# ES1050.net
KiCad netlist of a schematic drawn in Altium Designer
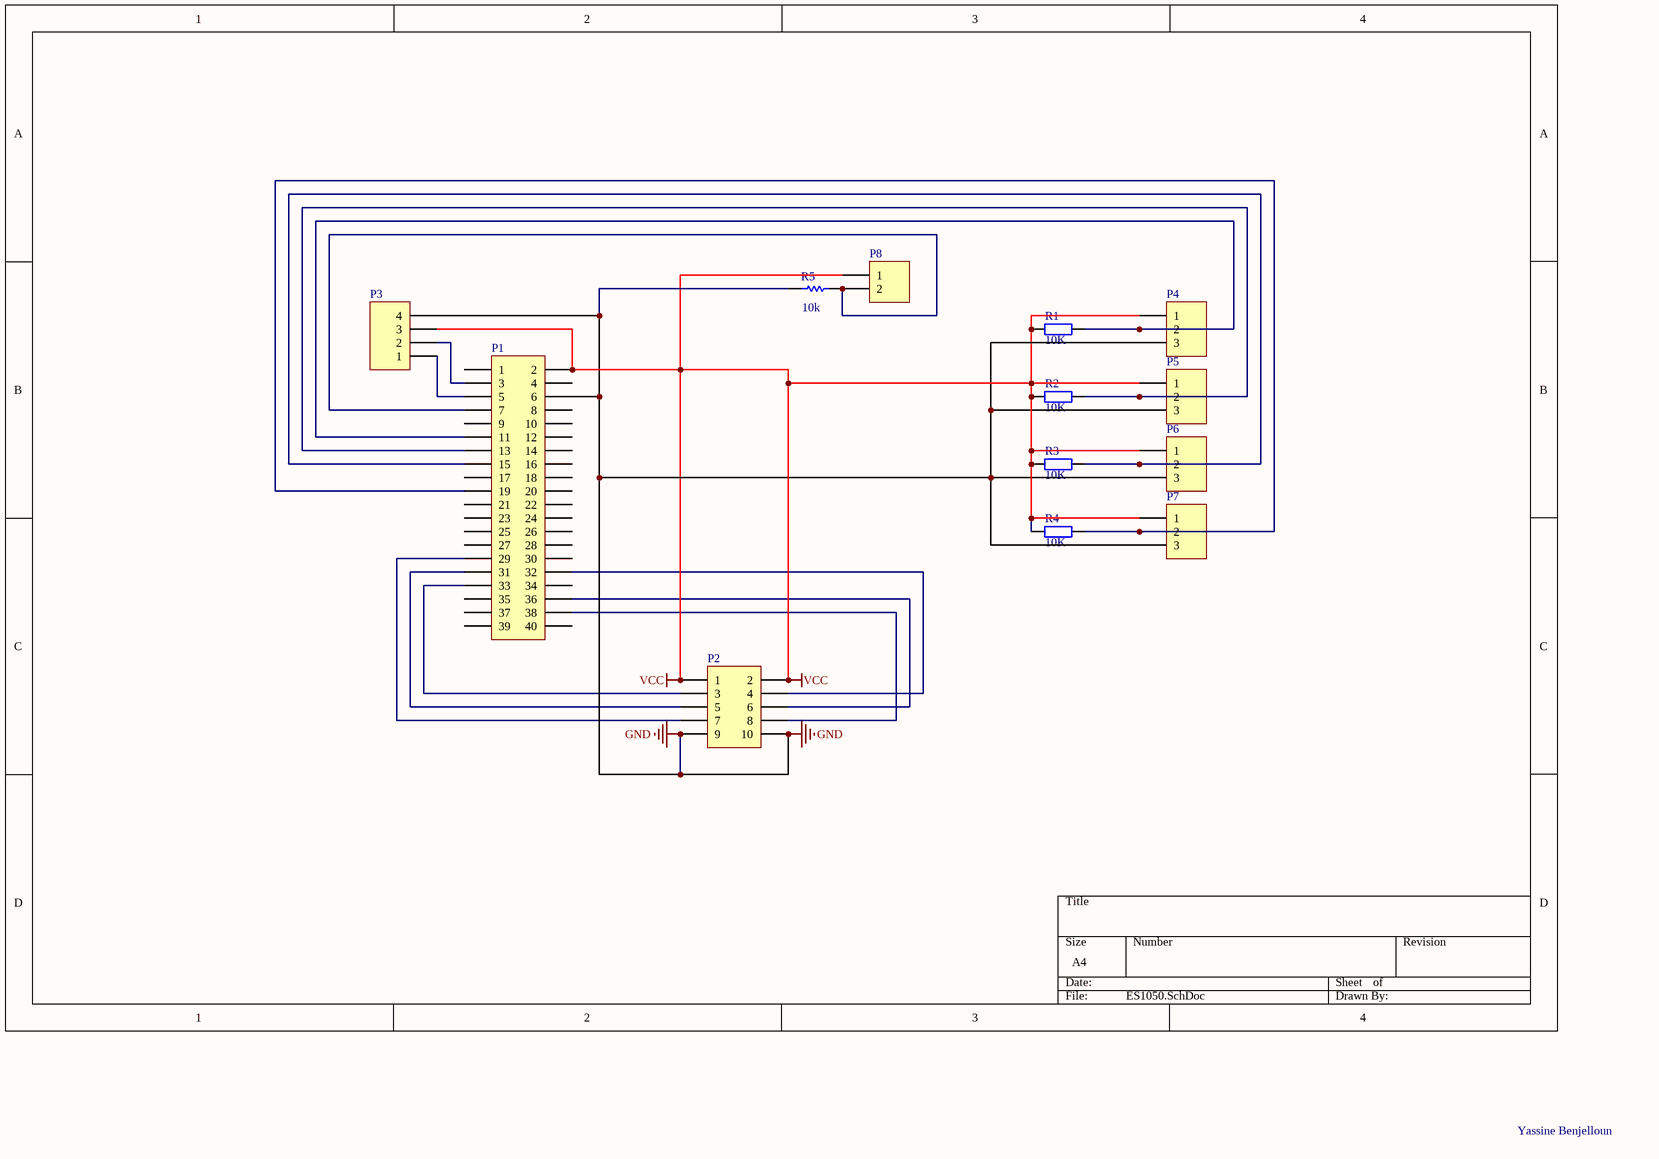
[diagram p0: ES1050.SchDoc]

(export (version "E")
  (design (tool "Eeschema 10.0.6"))
  (components
    (comp (ref "P1")
      (value "Header 20X2")
      (footprint "HDR2X20")
      (description "Header, 20-Pin, Dual row")
      (fields (field (name "PUBLISHER") "Altium Limited"))
      (libsource (lib "Miscellaneous Connectors") (part "Header 20X2"))
    )
    (comp (ref "P2")
      (value "Header 5X2")
      (footprint "HDR2X5")
      (description "Header, 5-Pin, Dual row")
      (fields (field (name "PUBLISHER") "Altium Limited"))
      (libsource (lib "Miscellaneous Connectors") (part "Header 5X2"))
    )
    (comp (ref "P3")
      (value "Header 4H")
      (footprint "HDR1X4H")
      (description "Header, 4-Pin, Right Angle")
      (fields (field (name "PUBLISHER") "Altium Limited"))
      (libsource (lib "Miscellaneous Connectors") (part "Header 4H"))
    )
    (comp (ref "P4")
      (value "Header 3")
      (footprint "HDR1X3")
      (description "Header, 3-Pin")
      (fields (field (name "PUBLISHER") "Altium Limited"))
      (libsource (lib "Miscellaneous Connectors") (part "Header 3"))
    )
    (comp (ref "P5")
      (value "Header 3")
      (footprint "HDR1X3")
      (description "Header, 3-Pin")
      (fields (field (name "PUBLISHER") "Altium Limited"))
      (libsource (lib "Miscellaneous Connectors") (part "Header 3"))
    )
    (comp (ref "P6")
      (value "Header 3")
      (footprint "HDR1X3")
      (description "Header, 3-Pin")
      (fields (field (name "PUBLISHER") "Altium Limited"))
      (libsource (lib "Miscellaneous Connectors") (part "Header 3"))
    )
    (comp (ref "P7")
      (value "Header 3")
      (footprint "HDR1X3")
      (description "Header, 3-Pin")
      (fields (field (name "PUBLISHER") "Altium Limited"))
      (libsource (lib "Miscellaneous Connectors") (part "Header 3"))
    )
    (comp (ref "P8")
      (value "Header 2")
      (footprint "HDR1X2")
      (description "Header, 2-Pin")
      (fields (field (name "PUBLISHER") "Altium Limited"))
      (libsource (lib "Miscellaneous Connectors") (part "Header 2"))
    )
    (comp (ref "R1")
      (value "10K")
      (footprint "AXIAL-0.4")
      (description "Resistor")
      (fields (field (name "Comment") "Res2") (field (name "PUBLISHER") "Altium Limited"))
      (libsource (lib "Miscellaneous Devices") (part "Res2"))
    )
    (comp (ref "R2")
      (value "10K")
      (footprint "AXIAL-0.4")
      (description "Resistor")
      (fields (field (name "Comment") "Res2") (field (name "PUBLISHER") "Altium Limited"))
      (libsource (lib "Miscellaneous Devices") (part "Res2"))
    )
    (comp (ref "R3")
      (value "10K")
      (footprint "AXIAL-0.4")
      (description "Resistor")
      (fields (field (name "Comment") "Res2") (field (name "PUBLISHER") "Altium Limited"))
      (libsource (lib "Miscellaneous Devices") (part "Res2"))
    )
    (comp (ref "R4")
      (value "10K")
      (footprint "AXIAL-0.4")
      (description "Resistor")
      (fields (field (name "Comment") "Res2") (field (name "PUBLISHER") "Altium Limited"))
      (libsource (lib "Miscellaneous Devices") (part "Res2"))
    )
    (comp (ref "R5")
      (value "10k")
      (footprint "AXIAL-0.4")
      (description "Resistor")
      (fields (field (name "Comment") "Res2") (field (name "PUBLISHER") "Altium Limited"))
      (libsource (lib "Miscellaneous Devices") (part "Res1"))
    )
  )
  (nets
    (net (code "1") (name "GND") (class "Default")
      (node (ref "P1") (pin "6") (pinfunction "6_6") (pintype "passive"))
      (node (ref "P2") (pin "10") (pinfunction "10_10") (pintype "passive"))
      (node (ref "P2") (pin "9") (pinfunction "9_9") (pintype "passive"))
      (node (ref "P3") (pin "4") (pinfunction "4_4") (pintype "passive"))
      (node (ref "P4") (pin "3") (pinfunction "3_3") (pintype "passive"))
      (node (ref "P5") (pin "3") (pinfunction "3_3") (pintype "passive"))
      (node (ref "P6") (pin "3") (pinfunction "3_3") (pintype "passive"))
      (node (ref "P7") (pin "3") (pinfunction "3_3") (pintype "passive"))
      (node (ref "R5") (pin "1") (pinfunction "1_1") (pintype "passive"))
    )
    (net (code "2") (name "Net-(P1-Pad3)") (class "Default")
      (node (ref "P1") (pin "3") (pinfunction "3_3") (pintype "passive"))
      (node (ref "P3") (pin "2") (pinfunction "2_2") (pintype "passive"))
    )
    (net (code "3") (name "Net-(P1-Pad5)") (class "Default")
      (node (ref "P1") (pin "5") (pinfunction "5_5") (pintype "passive"))
      (node (ref "P3") (pin "1") (pinfunction "1_1") (pintype "passive"))
    )
    (net (code "4") (name "Net-(P1-Pad7)") (class "Default")
      (node (ref "P1") (pin "7") (pinfunction "7_7") (pintype "passive"))
      (node (ref "P8") (pin "2") (pinfunction "2_2") (pintype "passive"))
      (node (ref "R5") (pin "2") (pinfunction "2_2") (pintype "passive"))
    )
    (net (code "5") (name "Net-(P1-Pad11)") (class "Default")
      (node (ref "P1") (pin "11") (pinfunction "11_11") (pintype "passive"))
      (node (ref "P4") (pin "2") (pinfunction "2_2") (pintype "passive"))
      (node (ref "R1") (pin "2") (pinfunction "2_2") (pintype "passive"))
    )
    (net (code "6") (name "Net-(P1-Pad13)") (class "Default")
      (node (ref "P1") (pin "13") (pinfunction "13_13") (pintype "passive"))
      (node (ref "P5") (pin "2") (pinfunction "2_2") (pintype "passive"))
      (node (ref "R2") (pin "2") (pinfunction "2_2") (pintype "passive"))
    )
    (net (code "7") (name "Net-(P1-Pad15)") (class "Default")
      (node (ref "P1") (pin "15") (pinfunction "15_15") (pintype "passive"))
      (node (ref "P6") (pin "2") (pinfunction "2_2") (pintype "passive"))
      (node (ref "R3") (pin "2") (pinfunction "2_2") (pintype "passive"))
    )
    (net (code "8") (name "Net-(P1-Pad19)") (class "Default")
      (node (ref "P1") (pin "19") (pinfunction "19_19") (pintype "passive"))
      (node (ref "P7") (pin "2") (pinfunction "2_2") (pintype "passive"))
      (node (ref "R4") (pin "2") (pinfunction "2_2") (pintype "passive"))
    )
    (net (code "9") (name "Net-(P1-Pad29)") (class "Default")
      (node (ref "P1") (pin "29") (pinfunction "29_29") (pintype "passive"))
      (node (ref "P2") (pin "7") (pinfunction "7_7") (pintype "passive"))
    )
    (net (code "10") (name "Net-(P1-Pad31)") (class "Default")
      (node (ref "P1") (pin "31") (pinfunction "31_31") (pintype "passive"))
      (node (ref "P2") (pin "5") (pinfunction "5_5") (pintype "passive"))
    )
    (net (code "11") (name "Net-(P1-Pad32)") (class "Default")
      (node (ref "P1") (pin "32") (pinfunction "32_32") (pintype "passive"))
      (node (ref "P2") (pin "4") (pinfunction "4_4") (pintype "passive"))
    )
    (net (code "12") (name "Net-(P1-Pad33)") (class "Default")
      (node (ref "P1") (pin "33") (pinfunction "33_33") (pintype "passive"))
      (node (ref "P2") (pin "3") (pinfunction "3_3") (pintype "passive"))
    )
    (net (code "13") (name "Net-(P1-Pad36)") (class "Default")
      (node (ref "P1") (pin "36") (pinfunction "36_36") (pintype "passive"))
      (node (ref "P2") (pin "6") (pinfunction "6_6") (pintype "passive"))
    )
    (net (code "14") (name "Net-(P1-Pad38)") (class "Default")
      (node (ref "P1") (pin "38") (pinfunction "38_38") (pintype "passive"))
      (node (ref "P2") (pin "8") (pinfunction "8_8") (pintype "passive"))
    )
    (net (code "15") (name "VCC") (class "Default")
      (node (ref "P1") (pin "2") (pinfunction "2_2") (pintype "passive"))
      (node (ref "P2") (pin "1") (pinfunction "1_1") (pintype "passive"))
      (node (ref "P2") (pin "2") (pinfunction "2_2") (pintype "passive"))
      (node (ref "P3") (pin "3") (pinfunction "3_3") (pintype "passive"))
      (node (ref "P4") (pin "1") (pinfunction "1_1") (pintype "passive"))
      (node (ref "P5") (pin "1") (pinfunction "1_1") (pintype "passive"))
      (node (ref "P6") (pin "1") (pinfunction "1_1") (pintype "passive"))
      (node (ref "P7") (pin "1") (pinfunction "1_1") (pintype "passive"))
      (node (ref "P8") (pin "1") (pinfunction "1_1") (pintype "passive"))
      (node (ref "R1") (pin "1") (pinfunction "1_1") (pintype "passive"))
      (node (ref "R2") (pin "1") (pinfunction "1_1") (pintype "passive"))
      (node (ref "R3") (pin "1") (pinfunction "1_1") (pintype "passive"))
      (node (ref "R4") (pin "1") (pinfunction "1_1") (pintype "passive"))
    )
    (net (code "16") (name "unconnected-(P1-Pad1)") (class "Default")
      (node (ref "P1") (pin "1") (pinfunction "1_1") (pintype "passive"))
    )
    (net (code "17") (name "unconnected-(P1-Pad4)") (class "Default")
      (node (ref "P1") (pin "4") (pinfunction "4_4") (pintype "passive"))
    )
    (net (code "18") (name "unconnected-(P1-Pad8)") (class "Default")
      (node (ref "P1") (pin "8") (pinfunction "8_8") (pintype "passive"))
    )
    (net (code "19") (name "unconnected-(P1-Pad9)") (class "Default")
      (node (ref "P1") (pin "9") (pinfunction "9_9") (pintype "passive"))
    )
    (net (code "20") (name "unconnected-(P1-Pad10)") (class "Default")
      (node (ref "P1") (pin "10") (pinfunction "10_10") (pintype "passive"))
    )
    (net (code "21") (name "unconnected-(P1-Pad12)") (class "Default")
      (node (ref "P1") (pin "12") (pinfunction "12_12") (pintype "passive"))
    )
    (net (code "22") (name "unconnected-(P1-Pad14)") (class "Default")
      (node (ref "P1") (pin "14") (pinfunction "14_14") (pintype "passive"))
    )
    (net (code "23") (name "unconnected-(P1-Pad16)") (class "Default")
      (node (ref "P1") (pin "16") (pinfunction "16_16") (pintype "passive"))
    )
    (net (code "24") (name "unconnected-(P1-Pad17)") (class "Default")
      (node (ref "P1") (pin "17") (pinfunction "17_17") (pintype "passive"))
    )
    (net (code "25") (name "unconnected-(P1-Pad18)") (class "Default")
      (node (ref "P1") (pin "18") (pinfunction "18_18") (pintype "passive"))
    )
    (net (code "26") (name "unconnected-(P1-Pad20)") (class "Default")
      (node (ref "P1") (pin "20") (pinfunction "20_20") (pintype "passive"))
    )
    (net (code "27") (name "unconnected-(P1-Pad21)") (class "Default")
      (node (ref "P1") (pin "21") (pinfunction "21_21") (pintype "passive"))
    )
    (net (code "28") (name "unconnected-(P1-Pad22)") (class "Default")
      (node (ref "P1") (pin "22") (pinfunction "22_22") (pintype "passive"))
    )
    (net (code "29") (name "unconnected-(P1-Pad23)") (class "Default")
      (node (ref "P1") (pin "23") (pinfunction "23_23") (pintype "passive"))
    )
    (net (code "30") (name "unconnected-(P1-Pad24)") (class "Default")
      (node (ref "P1") (pin "24") (pinfunction "24_24") (pintype "passive"))
    )
    (net (code "31") (name "unconnected-(P1-Pad25)") (class "Default")
      (node (ref "P1") (pin "25") (pinfunction "25_25") (pintype "passive"))
    )
    (net (code "32") (name "unconnected-(P1-Pad26)") (class "Default")
      (node (ref "P1") (pin "26") (pinfunction "26_26") (pintype "passive"))
    )
    (net (code "33") (name "unconnected-(P1-Pad27)") (class "Default")
      (node (ref "P1") (pin "27") (pinfunction "27_27") (pintype "passive"))
    )
    (net (code "34") (name "unconnected-(P1-Pad28)") (class "Default")
      (node (ref "P1") (pin "28") (pinfunction "28_28") (pintype "passive"))
    )
    (net (code "35") (name "unconnected-(P1-Pad30)") (class "Default")
      (node (ref "P1") (pin "30") (pinfunction "30_30") (pintype "passive"))
    )
    (net (code "36") (name "unconnected-(P1-Pad34)") (class "Default")
      (node (ref "P1") (pin "34") (pinfunction "34_34") (pintype "passive"))
    )
    (net (code "37") (name "unconnected-(P1-Pad35)") (class "Default")
      (node (ref "P1") (pin "35") (pinfunction "35_35") (pintype "passive"))
    )
    (net (code "38") (name "unconnected-(P1-Pad37)") (class "Default")
      (node (ref "P1") (pin "37") (pinfunction "37_37") (pintype "passive"))
    )
    (net (code "39") (name "unconnected-(P1-Pad39)") (class "Default")
      (node (ref "P1") (pin "39") (pinfunction "39_39") (pintype "passive"))
    )
    (net (code "40") (name "unconnected-(P1-Pad40)") (class "Default")
      (node (ref "P1") (pin "40") (pinfunction "40_40") (pintype "passive"))
    )
  )
)
